# lpc11u24mini.net
KiCad netlist of a schematic drawn in EAGLE
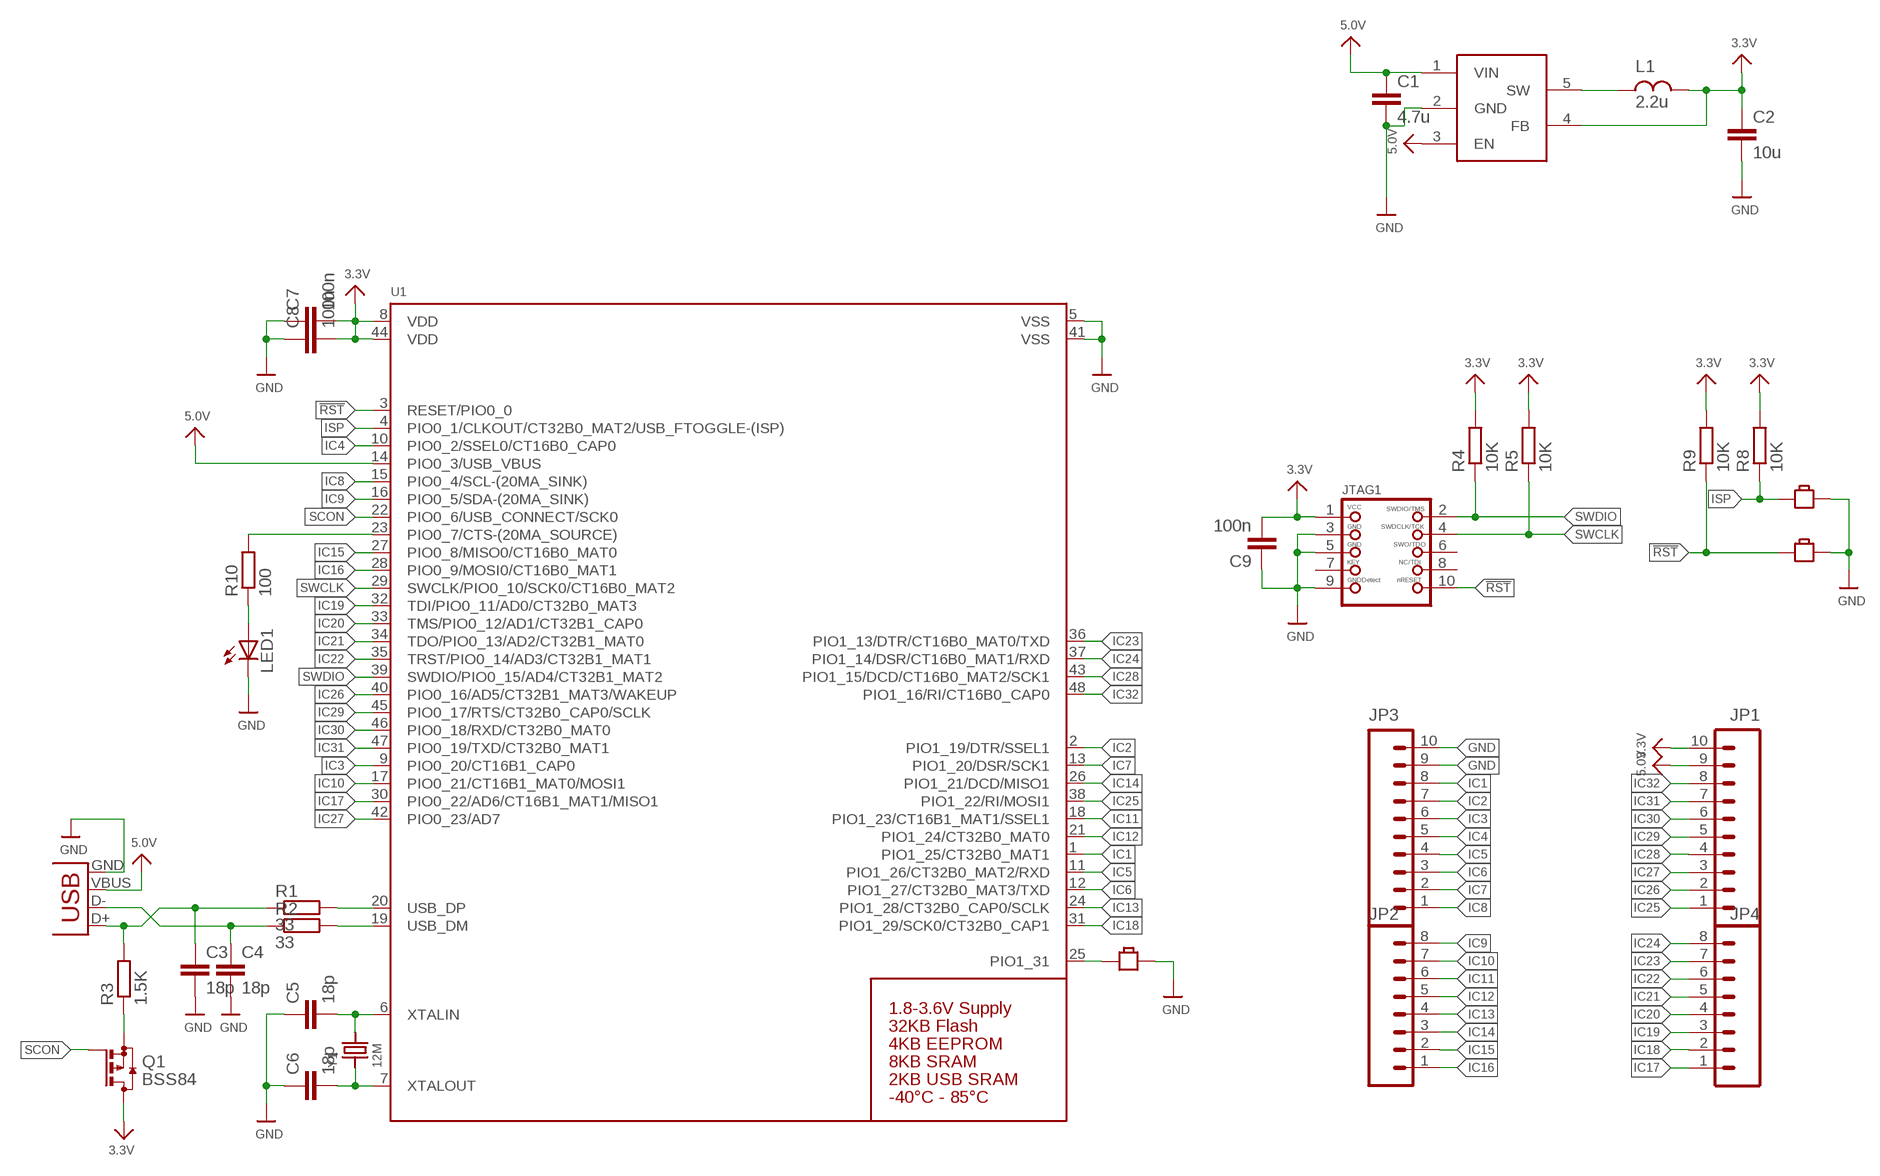
[diagram p0: schematic, sheet 1]

(export (version "E")
  (design (tool "Eeschema 10.0.6"))
  (components
    (comp (ref "B1")
      (value "BUTTON-SMD-2P")
      (footprint "eagle-import:BUTTON_2P_SMD")
      (libsource (lib "eagle-import") (part "BUTTON-SMD-2P"))
    )
    (comp (ref "B2")
      (value "BUTTON-SMD-2P")
      (footprint "eagle-import:BUTTON_2P_SMD")
      (libsource (lib "eagle-import") (part "BUTTON-SMD-2P"))
    )
    (comp (ref "B3")
      (value "BUTTON-SMD-2P")
      (footprint "eagle-import:BUTTON_2P_SMD")
      (libsource (lib "eagle-import") (part "BUTTON-SMD-2P"))
    )
    (comp (ref "C1")
      (value "4.7u")
      (footprint "eagle-import:C0603")
      (libsource (lib "eagle-import") (part "C-EUC0603"))
    )
    (comp (ref "C2")
      (value "10u")
      (footprint "eagle-import:C0603")
      (libsource (lib "eagle-import") (part "C-EUC0603"))
    )
    (comp (ref "C3")
      (value "18p")
      (footprint "eagle-import:C0603")
      (libsource (lib "eagle-import") (part "C-EUC0603"))
    )
    (comp (ref "C4")
      (value "18p")
      (footprint "eagle-import:C0603")
      (libsource (lib "eagle-import") (part "C-EUC0603"))
    )
    (comp (ref "C5")
      (value "18p")
      (footprint "eagle-import:C0603")
      (libsource (lib "eagle-import") (part "C-EUC0603"))
    )
    (comp (ref "C6")
      (value "18p")
      (footprint "eagle-import:C0603")
      (libsource (lib "eagle-import") (part "C-EUC0603"))
    )
    (comp (ref "C7")
      (value "100n")
      (footprint "eagle-import:C0603")
      (libsource (lib "eagle-import") (part "C-EUC0603"))
    )
    (comp (ref "C8")
      (value "100n")
      (footprint "eagle-import:C0603")
      (libsource (lib "eagle-import") (part "C-EUC0603"))
    )
    (comp (ref "C9")
      (value "100n")
      (footprint "eagle-import:C0603")
      (libsource (lib "eagle-import") (part "C-EUC0603"))
    )
    (comp (ref "JP1")
      (value "M10SMD_MALE")
      (footprint "eagle-import:1X10_SMD_MALE")
      (libsource (lib "eagle-import") (part "M10SMD_MALE"))
    )
    (comp (ref "JP2")
      (value "M08SMD-MALE")
      (footprint "eagle-import:1X08_SMD_MALE")
      (libsource (lib "eagle-import") (part "M08SMD-MALE"))
    )
    (comp (ref "JP3")
      (value "M10SMD_MALE")
      (footprint "eagle-import:1X10_SMD_MALE")
      (libsource (lib "eagle-import") (part "M10SMD_MALE"))
    )
    (comp (ref "JP4")
      (value "M08SMD-MALE")
      (footprint "eagle-import:1X08_SMD_MALE")
      (libsource (lib "eagle-import") (part "M08SMD-MALE"))
    )
    (comp (ref "JTAG1")
      (value "JTAG-CORTEXM3")
      (footprint "eagle-import:2X05_1.27MM_SMT")
      (libsource (lib "eagle-import") (part "JTAG-CORTEXM3"))
    )
    (comp (ref "L1")
      (value "2.2u")
      (footprint "eagle-import:SRN2512")
      (libsource (lib "eagle-import") (part "L_SNR2512"))
    )
    (comp (ref "LED1")
      (value "LEDSML0805")
      (footprint "eagle-import:SML0805")
      (libsource (lib "eagle-import") (part "LEDSML0805"))
    )
    (comp (ref "Q1")
      (value "BSS84")
      (footprint "eagle-import:SOT23")
      (libsource (lib "eagle-import") (part "BSS84"))
    )
    (comp (ref "R1")
      (value "33")
      (footprint "eagle-import:R0603")
      (libsource (lib "eagle-import") (part "R-EU_R0603"))
    )
    (comp (ref "R2")
      (value "33")
      (footprint "eagle-import:R0603")
      (libsource (lib "eagle-import") (part "R-EU_R0603"))
    )
    (comp (ref "R3")
      (value "1.5K")
      (footprint "eagle-import:R0603")
      (libsource (lib "eagle-import") (part "R-EU_R0603"))
    )
    (comp (ref "R4")
      (value "10K")
      (footprint "eagle-import:R0603")
      (libsource (lib "eagle-import") (part "R-EU_R0603"))
    )
    (comp (ref "R5")
      (value "10K")
      (footprint "eagle-import:R0603")
      (libsource (lib "eagle-import") (part "R-EU_R0603"))
    )
    (comp (ref "R8")
      (value "10K")
      (footprint "eagle-import:R0603")
      (libsource (lib "eagle-import") (part "R-EU_R0603"))
    )
    (comp (ref "R9")
      (value "10K")
      (footprint "eagle-import:R0603")
      (libsource (lib "eagle-import") (part "R-EU_R0603"))
    )
    (comp (ref "R10")
      (value "100")
      (footprint "eagle-import:R0603")
      (libsource (lib "eagle-import") (part "R-EU_R0603"))
    )
    (comp (ref "U$3")
      (value "LM3671")
      (footprint "eagle-import:SOT23-5")
      (libsource (lib "eagle-import") (part "LM3671"))
    )
    (comp (ref "U1")
      (value "LPC11U24_QFP48")
      (footprint "eagle-import:LQFP48")
      (libsource (lib "eagle-import") (part "LPC11U24_QFP48"))
    )
    (comp (ref "X1")
      (value "USB-MICROB")
      (footprint "eagle-import:USB-MICROB")
      (libsource (lib "eagle-import") (part "USB-MICROB"))
    )
    (comp (ref "Y1")
      (value "12M")
      (footprint "eagle-import:CRYSTAL_3.2X2.5")
      (libsource (lib "eagle-import") (part "CRYSTALTHIN"))
    )
  )
  (nets
    (net (code "1") (name "/~{RST}") (class "Default")
      (node (ref "B2") (pin "1") (pinfunction "P$1_1") (pintype "bidirectional"))
      (node (ref "JTAG1") (pin "10") (pinfunction "10_10") (pintype "passive"))
      (node (ref "R9") (pin "1") (pinfunction "1_1") (pintype "passive"))
      (node (ref "U1") (pin "3") (pinfunction "RESET/PIO0_0_3") (pintype "bidirectional"))
    )
    (net (code "2") (name "3.3V") (class "Default")
      (node (ref "C2") (pin "1") (pinfunction "1_1") (pintype "passive"))
      (node (ref "C7") (pin "2") (pinfunction "2_2") (pintype "passive"))
      (node (ref "C8") (pin "2") (pinfunction "2_2") (pintype "passive"))
      (node (ref "C9") (pin "2") (pinfunction "2_2") (pintype "passive"))
      (node (ref "JP1") (pin "10") (pinfunction "10_10") (pintype "passive"))
      (node (ref "JTAG1") (pin "1") (pinfunction "1_1") (pintype "passive"))
      (node (ref "L1") (pin "P$2") (pinfunction "2_P$2") (pintype "passive"))
      (node (ref "Q1") (pin "3") (pinfunction "D_3") (pintype "passive"))
      (node (ref "R4") (pin "2") (pinfunction "2_2") (pintype "passive"))
      (node (ref "R5") (pin "2") (pinfunction "2_2") (pintype "passive"))
      (node (ref "R8") (pin "2") (pinfunction "2_2") (pintype "passive"))
      (node (ref "R9") (pin "2") (pinfunction "2_2") (pintype "passive"))
      (node (ref "U$3") (pin "4") (pinfunction "FB_4") (pintype "bidirectional"))
      (node (ref "U1") (pin "44") (pinfunction "VDD_44") (pintype "bidirectional"))
      (node (ref "U1") (pin "8") (pinfunction "VDD_8") (pintype "bidirectional"))
    )
    (net (code "3") (name "5.0V") (class "Default")
      (node (ref "C1") (pin "1") (pinfunction "1_1") (pintype "passive"))
      (node (ref "JP1") (pin "9") (pinfunction "9_9") (pintype "passive"))
      (node (ref "U$3") (pin "1") (pinfunction "VIN_1") (pintype "bidirectional"))
      (node (ref "U$3") (pin "3") (pinfunction "EN_3") (pintype "bidirectional"))
      (node (ref "U1") (pin "14") (pinfunction "PIO0_3/USB_VBUS_14") (pintype "bidirectional"))
      (node (ref "X1") (pin "VBUS") (pinfunction "VBUS_VBUS") (pintype "bidirectional"))
    )
    (net (code "4") (name "GND") (class "Default")
      (node (ref "B1") (pin "P$2") (pinfunction "P$2_P$2") (pintype "bidirectional"))
      (node (ref "B2") (pin "P$2") (pinfunction "P$2_P$2") (pintype "bidirectional"))
      (node (ref "B3") (pin "P$2") (pinfunction "P$2_P$2") (pintype "bidirectional"))
      (node (ref "C1") (pin "2") (pinfunction "2_2") (pintype "passive"))
      (node (ref "C2") (pin "2") (pinfunction "2_2") (pintype "passive"))
      (node (ref "C3") (pin "2") (pinfunction "2_2") (pintype "passive"))
      (node (ref "C4") (pin "2") (pinfunction "2_2") (pintype "passive"))
      (node (ref "C5") (pin "1") (pinfunction "1_1") (pintype "passive"))
      (node (ref "C6") (pin "1") (pinfunction "1_1") (pintype "passive"))
      (node (ref "C7") (pin "1") (pinfunction "1_1") (pintype "passive"))
      (node (ref "C8") (pin "1") (pinfunction "1_1") (pintype "passive"))
      (node (ref "C9") (pin "1") (pinfunction "1_1") (pintype "passive"))
      (node (ref "JP3") (pin "10") (pinfunction "10_10") (pintype "passive"))
      (node (ref "JP3") (pin "9") (pinfunction "9_9") (pintype "passive"))
      (node (ref "JTAG1") (pin "3") (pinfunction "3_3") (pintype "passive"))
      (node (ref "JTAG1") (pin "5") (pinfunction "5_5") (pintype "passive"))
      (node (ref "JTAG1") (pin "9") (pinfunction "9_9") (pintype "passive"))
      (node (ref "LED1") (pin "C") (pinfunction "C_C") (pintype "passive"))
      (node (ref "U$3") (pin "2") (pinfunction "GND_2") (pintype "bidirectional"))
      (node (ref "U1") (pin "41") (pinfunction "VSS_41") (pintype "bidirectional"))
      (node (ref "U1") (pin "5") (pinfunction "VSS_5") (pintype "bidirectional"))
      (node (ref "X1") (pin "GND") (pinfunction "GND_GND") (pintype "bidirectional"))
    )
    (net (code "5") (name "IC1") (class "Default")
      (node (ref "JP3") (pin "8") (pinfunction "8_8") (pintype "passive"))
      (node (ref "U1") (pin "1") (pinfunction "PIO1_25/CT32B0_MAT1_1") (pintype "bidirectional"))
    )
    (net (code "6") (name "IC2") (class "Default")
      (node (ref "JP3") (pin "7") (pinfunction "7_7") (pintype "passive"))
      (node (ref "U1") (pin "2") (pinfunction "PIO1_19/DTR/SSEL1_2") (pintype "bidirectional"))
    )
    (net (code "7") (name "IC3") (class "Default")
      (node (ref "JP3") (pin "6") (pinfunction "6_6") (pintype "passive"))
      (node (ref "U1") (pin "9") (pinfunction "PIO0_20/CT16B1_CAP0_9") (pintype "bidirectional"))
    )
    (net (code "8") (name "IC4") (class "Default")
      (node (ref "JP3") (pin "5") (pinfunction "5_5") (pintype "passive"))
      (node (ref "U1") (pin "10") (pinfunction "PIO0_2/SSEL0/CT16B0_CAP0_10") (pintype "bidirectional"))
    )
    (net (code "9") (name "IC5") (class "Default")
      (node (ref "JP3") (pin "4") (pinfunction "4_4") (pintype "passive"))
      (node (ref "U1") (pin "11") (pinfunction "PIO1_26/CT32B0_MAT2/RXD_11") (pintype "bidirectional"))
    )
    (net (code "10") (name "IC6") (class "Default")
      (node (ref "JP3") (pin "3") (pinfunction "3_3") (pintype "passive"))
      (node (ref "U1") (pin "12") (pinfunction "PIO1_27/CT32B0_MAT3/TXD_12") (pintype "bidirectional"))
    )
    (net (code "11") (name "IC7") (class "Default")
      (node (ref "JP3") (pin "2") (pinfunction "2_2") (pintype "passive"))
      (node (ref "U1") (pin "13") (pinfunction "PIO1_20/DSR/SCK1_13") (pintype "bidirectional"))
    )
    (net (code "12") (name "IC8") (class "Default")
      (node (ref "JP3") (pin "1") (pinfunction "1_1") (pintype "passive"))
      (node (ref "U1") (pin "15") (pinfunction "PIO0_4/SCL-(20MA_SINK)_15") (pintype "bidirectional"))
    )
    (net (code "13") (name "IC9") (class "Default")
      (node (ref "JP2") (pin "8") (pinfunction "8_8") (pintype "passive"))
      (node (ref "U1") (pin "16") (pinfunction "PIO0_5/SDA-(20MA_SINK)_16") (pintype "bidirectional"))
    )
    (net (code "14") (name "IC10") (class "Default")
      (node (ref "JP2") (pin "7") (pinfunction "7_7") (pintype "passive"))
      (node (ref "U1") (pin "17") (pinfunction "PIO0_21/CT16B1_MAT0/MOSI1_17") (pintype "bidirectional"))
    )
    (net (code "15") (name "IC11") (class "Default")
      (node (ref "JP2") (pin "6") (pinfunction "6_6") (pintype "passive"))
      (node (ref "U1") (pin "18") (pinfunction "PIO1_23/CT16B1_MAT1/SSEL1_18") (pintype "bidirectional"))
    )
    (net (code "16") (name "IC12") (class "Default")
      (node (ref "JP2") (pin "5") (pinfunction "5_5") (pintype "passive"))
      (node (ref "U1") (pin "21") (pinfunction "PIO1_24/CT32B0_MAT0_21") (pintype "bidirectional"))
    )
    (net (code "17") (name "IC13") (class "Default")
      (node (ref "JP2") (pin "4") (pinfunction "4_4") (pintype "passive"))
      (node (ref "U1") (pin "24") (pinfunction "PIO1_28/CT32B0_CAP0/SCLK_24") (pintype "bidirectional"))
    )
    (net (code "18") (name "IC14") (class "Default")
      (node (ref "JP2") (pin "3") (pinfunction "3_3") (pintype "passive"))
      (node (ref "U1") (pin "26") (pinfunction "PIO1_21/DCD/MISO1_26") (pintype "bidirectional"))
    )
    (net (code "19") (name "IC15") (class "Default")
      (node (ref "JP2") (pin "2") (pinfunction "2_2") (pintype "passive"))
      (node (ref "U1") (pin "27") (pinfunction "PIO0_8/MISO0/CT16B0_MAT0_27") (pintype "bidirectional"))
    )
    (net (code "20") (name "IC16") (class "Default")
      (node (ref "JP2") (pin "1") (pinfunction "1_1") (pintype "passive"))
      (node (ref "U1") (pin "28") (pinfunction "PIO0_9/MOSI0/CT16B0_MAT1_28") (pintype "bidirectional"))
    )
    (net (code "21") (name "IC17") (class "Default")
      (node (ref "JP4") (pin "1") (pinfunction "1_1") (pintype "passive"))
      (node (ref "U1") (pin "30") (pinfunction "PIO0_22/AD6/CT16B1_MAT1/MISO1_30") (pintype "bidirectional"))
    )
    (net (code "22") (name "IC18") (class "Default")
      (node (ref "JP4") (pin "2") (pinfunction "2_2") (pintype "passive"))
      (node (ref "U1") (pin "31") (pinfunction "PIO1_29/SCK0/CT32B0_CAP1_31") (pintype "bidirectional"))
    )
    (net (code "23") (name "IC19") (class "Default")
      (node (ref "JP4") (pin "3") (pinfunction "3_3") (pintype "passive"))
      (node (ref "U1") (pin "32") (pinfunction "TDI/PIO0_11/AD0/CT32B0_MAT3_32") (pintype "bidirectional"))
    )
    (net (code "24") (name "IC20") (class "Default")
      (node (ref "JP4") (pin "4") (pinfunction "4_4") (pintype "passive"))
      (node (ref "U1") (pin "33") (pinfunction "TMS/PIO0_12/AD1/CT32B1_CAP0_33") (pintype "bidirectional"))
    )
    (net (code "25") (name "IC21") (class "Default")
      (node (ref "JP4") (pin "5") (pinfunction "5_5") (pintype "passive"))
      (node (ref "U1") (pin "34") (pinfunction "TDO/PIO0_13/AD2/CT32B1_MAT0_34") (pintype "bidirectional"))
    )
    (net (code "26") (name "IC22") (class "Default")
      (node (ref "JP4") (pin "6") (pinfunction "6_6") (pintype "passive"))
      (node (ref "U1") (pin "35") (pinfunction "TRST/PIO0_14/AD3/CT32B1_MAT1_35") (pintype "bidirectional"))
    )
    (net (code "27") (name "IC23") (class "Default")
      (node (ref "JP4") (pin "7") (pinfunction "7_7") (pintype "passive"))
      (node (ref "U1") (pin "36") (pinfunction "PIO1_13/DTR/CT16B0_MAT0/TXD_36") (pintype "bidirectional"))
    )
    (net (code "28") (name "IC24") (class "Default")
      (node (ref "JP4") (pin "8") (pinfunction "8_8") (pintype "passive"))
      (node (ref "U1") (pin "37") (pinfunction "PIO1_14/DSR/CT16B0_MAT1/RXD_37") (pintype "bidirectional"))
    )
    (net (code "29") (name "IC25") (class "Default")
      (node (ref "JP1") (pin "1") (pinfunction "1_1") (pintype "passive"))
      (node (ref "U1") (pin "38") (pinfunction "PIO1_22/RI/MOSI1_38") (pintype "bidirectional"))
    )
    (net (code "30") (name "IC26") (class "Default")
      (node (ref "JP1") (pin "2") (pinfunction "2_2") (pintype "passive"))
      (node (ref "U1") (pin "40") (pinfunction "PIO0_16/AD5/CT32B1_MAT3/WAKEUP_40") (pintype "bidirectional"))
    )
    (net (code "31") (name "IC27") (class "Default")
      (node (ref "JP1") (pin "3") (pinfunction "3_3") (pintype "passive"))
      (node (ref "U1") (pin "42") (pinfunction "PIO0_23/AD7_42") (pintype "bidirectional"))
    )
    (net (code "32") (name "IC28") (class "Default")
      (node (ref "JP1") (pin "4") (pinfunction "4_4") (pintype "passive"))
      (node (ref "U1") (pin "43") (pinfunction "PIO1_15/DCD/CT16B0_MAT2/SCK1_43") (pintype "bidirectional"))
    )
    (net (code "33") (name "IC29") (class "Default")
      (node (ref "JP1") (pin "5") (pinfunction "5_5") (pintype "passive"))
      (node (ref "U1") (pin "45") (pinfunction "PIO0_17/RTS/CT32B0_CAP0/SCLK_45") (pintype "bidirectional"))
    )
    (net (code "34") (name "IC30") (class "Default")
      (node (ref "JP1") (pin "6") (pinfunction "6_6") (pintype "passive"))
      (node (ref "U1") (pin "46") (pinfunction "PIO0_18/RXD/CT32B0_MAT0_46") (pintype "bidirectional"))
    )
    (net (code "35") (name "IC31") (class "Default")
      (node (ref "JP1") (pin "7") (pinfunction "7_7") (pintype "passive"))
      (node (ref "U1") (pin "47") (pinfunction "PIO0_19/TXD/CT32B0_MAT1_47") (pintype "bidirectional"))
    )
    (net (code "36") (name "IC32") (class "Default")
      (node (ref "JP1") (pin "8") (pinfunction "8_8") (pintype "passive"))
      (node (ref "U1") (pin "48") (pinfunction "PIO1_16/RI/CT16B0_CAP0_48") (pintype "bidirectional"))
    )
    (net (code "37") (name "ISP") (class "Default")
      (node (ref "B1") (pin "1") (pinfunction "P$1_1") (pintype "bidirectional"))
      (node (ref "R8") (pin "1") (pinfunction "1_1") (pintype "passive"))
      (node (ref "U1") (pin "4") (pinfunction "PIO0_1/CLKOUT/CT32B0_MAT2/USB_FTOGGLE-(ISP)_4") (pintype "bidirectional"))
    )
    (net (code "38") (name "Net-(B3-P$1)") (class "Default")
      (node (ref "B3") (pin "1") (pinfunction "P$1_1") (pintype "bidirectional"))
      (node (ref "U1") (pin "25") (pinfunction "PIO1_31_25") (pintype "bidirectional"))
    )
    (net (code "39") (name "Net-(C3-Pad1)") (class "Default")
      (node (ref "C3") (pin "1") (pinfunction "1_1") (pintype "passive"))
      (node (ref "R1") (pin "1") (pinfunction "1_1") (pintype "passive"))
      (node (ref "R3") (pin "2") (pinfunction "2_2") (pintype "passive"))
      (node (ref "X1") (pin "D+") (pinfunction "D+_D+") (pintype "bidirectional"))
    )
    (net (code "40") (name "Net-(C4-Pad1)") (class "Default")
      (node (ref "C4") (pin "1") (pinfunction "1_1") (pintype "passive"))
      (node (ref "R2") (pin "1") (pinfunction "1_1") (pintype "passive"))
      (node (ref "X1") (pin "D-") (pinfunction "D-_D-") (pintype "bidirectional"))
    )
    (net (code "41") (name "Net-(L1-1)") (class "Default")
      (node (ref "L1") (pin "P$1") (pinfunction "1_P$1") (pintype "passive"))
      (node (ref "U$3") (pin "5") (pinfunction "SW_5") (pintype "bidirectional"))
    )
    (net (code "42") (name "Net-(LED1-PadA)") (class "Default")
      (node (ref "LED1") (pin "A") (pinfunction "A_A") (pintype "passive"))
      (node (ref "R10") (pin "1") (pinfunction "1_1") (pintype "passive"))
    )
    (net (code "43") (name "Net-(Q1-S)") (class "Default")
      (node (ref "Q1") (pin "2") (pinfunction "S_2") (pintype "passive"))
      (node (ref "R3") (pin "1") (pinfunction "1_1") (pintype "passive"))
    )
    (net (code "44") (name "Net-(U1-PIO0_7{slash}CTS-(20MA_SOURCE))") (class "Default")
      (node (ref "R10") (pin "2") (pinfunction "2_2") (pintype "passive"))
      (node (ref "U1") (pin "23") (pinfunction "PIO0_7/CTS-(20MA_SOURCE)_23") (pintype "bidirectional"))
    )
    (net (code "45") (name "Net-(U1-USB_DM)") (class "Default")
      (node (ref "R2") (pin "2") (pinfunction "2_2") (pintype "passive"))
      (node (ref "U1") (pin "19") (pinfunction "USB_DM_19") (pintype "bidirectional"))
    )
    (net (code "46") (name "Net-(U1-USB_DP)") (class "Default")
      (node (ref "R1") (pin "2") (pinfunction "2_2") (pintype "passive"))
      (node (ref "U1") (pin "20") (pinfunction "USB_DP_20") (pintype "bidirectional"))
    )
    (net (code "47") (name "Net-(U1-XTALIN)") (class "Default")
      (node (ref "C5") (pin "2") (pinfunction "2_2") (pintype "passive"))
      (node (ref "U1") (pin "6") (pinfunction "XTALIN_6") (pintype "bidirectional"))
      (node (ref "Y1") (pin "2") (pinfunction "2_2") (pintype "passive"))
    )
    (net (code "48") (name "Net-(U1-XTALOUT)") (class "Default")
      (node (ref "C6") (pin "2") (pinfunction "2_2") (pintype "passive"))
      (node (ref "U1") (pin "7") (pinfunction "XTALOUT_7") (pintype "bidirectional"))
      (node (ref "Y1") (pin "1") (pinfunction "1_1") (pintype "passive"))
    )
    (net (code "49") (name "SCON") (class "Default")
      (node (ref "Q1") (pin "1") (pinfunction "G_1") (pintype "passive"))
      (node (ref "U1") (pin "22") (pinfunction "PIO0_6/USB_CONNECT/SCK0_22") (pintype "bidirectional"))
    )
    (net (code "50") (name "SWCLK") (class "Default")
      (node (ref "JTAG1") (pin "4") (pinfunction "4_4") (pintype "passive"))
      (node (ref "R5") (pin "1") (pinfunction "1_1") (pintype "passive"))
      (node (ref "U1") (pin "29") (pinfunction "SWCLK/PIO0_10/SCK0/CT16B0_MAT2_29") (pintype "bidirectional"))
    )
    (net (code "51") (name "SWDIO") (class "Default")
      (node (ref "JTAG1") (pin "2") (pinfunction "2_2") (pintype "passive"))
      (node (ref "R4") (pin "1") (pinfunction "1_1") (pintype "passive"))
      (node (ref "U1") (pin "39") (pinfunction "SWDIO/PIO0_15/AD4/CT32B1_MAT2_39") (pintype "bidirectional"))
    )
    (net (code "52") (name "unconnected-(JTAG1-Pad6)") (class "Default")
      (node (ref "JTAG1") (pin "6") (pinfunction "6_6") (pintype "passive"))
    )
    (net (code "53") (name "unconnected-(JTAG1-Pad7)") (class "Default")
      (node (ref "JTAG1") (pin "7") (pinfunction "7_7") (pintype "passive"))
    )
    (net (code "54") (name "unconnected-(JTAG1-Pad8)") (class "Default")
      (node (ref "JTAG1") (pin "8") (pinfunction "8_8") (pintype "passive"))
    )
  )
)
